# 04_Input.net
KiCad netlist of a schematic drawn in Altium Designer
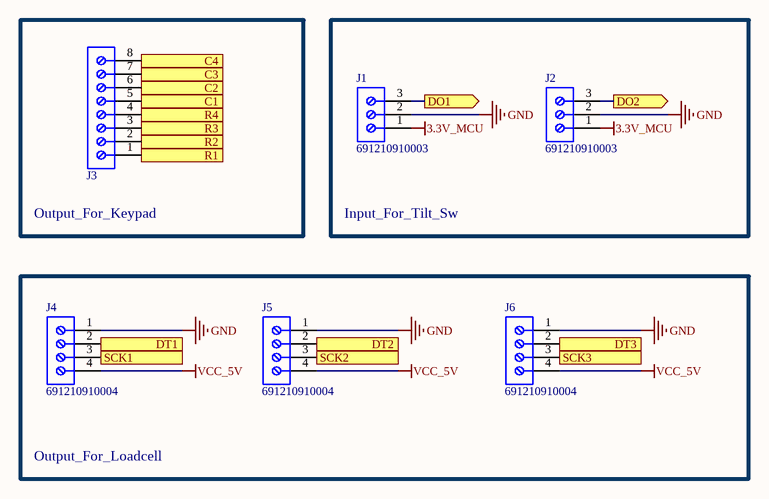
[diagram p0: 04_Input.SchDoc]

(export (version "E")
  (design (tool "Eeschema 10.0.6"))
  (components
    (comp (ref "J1")
      (value "691210910003")
      (footprint "691210910003")
      (description "WR-TBL Serie 2109 Horizontal Entry, Rising Cage Clamp, pitch 2.54mm, 3p")
      (fields (field (name "PUBLISHER") "Wurth Elektronik"))
      (libsource (lib "691322310002.") (part "691210910003"))
    )
    (comp (ref "J2")
      (value "691210910003")
      (footprint "691210910003")
      (description "WR-TBL Serie 2109 Horizontal Entry, Rising Cage Clamp, pitch 2.54mm, 3p")
      (fields (field (name "PUBLISHER") "Wurth Elektronik"))
      (libsource (lib "691322310002.") (part "691210910003"))
    )
    (comp (ref "J3")
      (value "691210910008")
      (footprint "691210910008")
      (description "WR-TBL Series 2109 Horizontal Entry, Through Hole, pitch 2.54mm, 8p")
      (fields (field (name "MANUFACTURER") "Wurth Elektronik"))
      (libsource (lib "Altium_WR-TBL (rev22a)") (part "691210910008"))
    )
    (comp (ref "J4")
      (value "691210910004")
      (footprint "691210910004")
      (description "WR-TBL Serie 2109 Horizontal Entry, Rising Cage Clamp, pitch 2.54mm, 4p")
      (fields (field (name "PUBLISHER") "Wurth Elektronik"))
      (libsource (lib "691322310002.") (part "691210910004"))
    )
    (comp (ref "J5")
      (value "691210910004")
      (footprint "691210910004")
      (description "WR-TBL Serie 2109 Horizontal Entry, Rising Cage Clamp, pitch 2.54mm, 4p")
      (fields (field (name "PUBLISHER") "Wurth Elektronik"))
      (libsource (lib "691322310002.") (part "691210910004"))
    )
    (comp (ref "J6")
      (value "691210910004")
      (footprint "691210910004")
      (description "WR-TBL Serie 2109 Horizontal Entry, Rising Cage Clamp, pitch 2.54mm, 4p")
      (fields (field (name "PUBLISHER") "Wurth Elektronik"))
      (libsource (lib "691322310002.") (part "691210910004"))
    )
  )
  (nets
    (net (code "1") (name "/C1") (class "Default")
      (node (ref "J3") (pin "5") (pinfunction "5_5") (pintype "passive"))
    )
    (net (code "2") (name "/C2") (class "Default")
      (node (ref "J3") (pin "6") (pinfunction "6_6") (pintype "passive"))
    )
    (net (code "3") (name "/C3") (class "Default")
      (node (ref "J3") (pin "7") (pinfunction "7_7") (pintype "passive"))
    )
    (net (code "4") (name "/C4") (class "Default")
      (node (ref "J3") (pin "8") (pinfunction "8_8") (pintype "passive"))
    )
    (net (code "5") (name "/DO1") (class "Default")
      (node (ref "J1") (pin "3") (pinfunction "3_3") (pintype "passive"))
    )
    (net (code "6") (name "/DO2") (class "Default")
      (node (ref "J2") (pin "3") (pinfunction "3_3") (pintype "passive"))
    )
    (net (code "7") (name "/DT1") (class "Default")
      (node (ref "J4") (pin "2") (pinfunction "2_2") (pintype "passive"))
    )
    (net (code "8") (name "/DT2") (class "Default")
      (node (ref "J5") (pin "2") (pinfunction "2_2") (pintype "passive"))
    )
    (net (code "9") (name "/DT3") (class "Default")
      (node (ref "J6") (pin "2") (pinfunction "2_2") (pintype "passive"))
    )
    (net (code "10") (name "/R1") (class "Default")
      (node (ref "J3") (pin "1") (pinfunction "1_1") (pintype "passive"))
    )
    (net (code "11") (name "/R2") (class "Default")
      (node (ref "J3") (pin "2") (pinfunction "2_2") (pintype "passive"))
    )
    (net (code "12") (name "/R3") (class "Default")
      (node (ref "J3") (pin "3") (pinfunction "3_3") (pintype "passive"))
    )
    (net (code "13") (name "/R4") (class "Default")
      (node (ref "J3") (pin "4") (pinfunction "4_4") (pintype "passive"))
    )
    (net (code "14") (name "/SCK1") (class "Default")
      (node (ref "J4") (pin "3") (pinfunction "3_3") (pintype "passive"))
    )
    (net (code "15") (name "/SCK2") (class "Default")
      (node (ref "J5") (pin "3") (pinfunction "3_3") (pintype "passive"))
    )
    (net (code "16") (name "/SCK3") (class "Default")
      (node (ref "J6") (pin "3") (pinfunction "3_3") (pintype "passive"))
    )
    (net (code "17") (name "3.3V_MCU") (class "Default")
      (node (ref "J1") (pin "1") (pinfunction "1_1") (pintype "passive"))
      (node (ref "J2") (pin "1") (pinfunction "1_1") (pintype "passive"))
    )
    (net (code "18") (name "GND") (class "Default")
      (node (ref "J1") (pin "2") (pinfunction "2_2") (pintype "passive"))
      (node (ref "J2") (pin "2") (pinfunction "2_2") (pintype "passive"))
      (node (ref "J4") (pin "1") (pinfunction "1_1") (pintype "passive"))
      (node (ref "J5") (pin "1") (pinfunction "1_1") (pintype "passive"))
      (node (ref "J6") (pin "1") (pinfunction "1_1") (pintype "passive"))
    )
    (net (code "19") (name "VCC_5V") (class "Default")
      (node (ref "J4") (pin "4") (pinfunction "4_4") (pintype "passive"))
      (node (ref "J5") (pin "4") (pinfunction "4_4") (pintype "passive"))
      (node (ref "J6") (pin "4") (pinfunction "4_4") (pintype "passive"))
    )
  )
)
